# Sheet2.net
KiCad netlist of a schematic drawn in Altium Designer
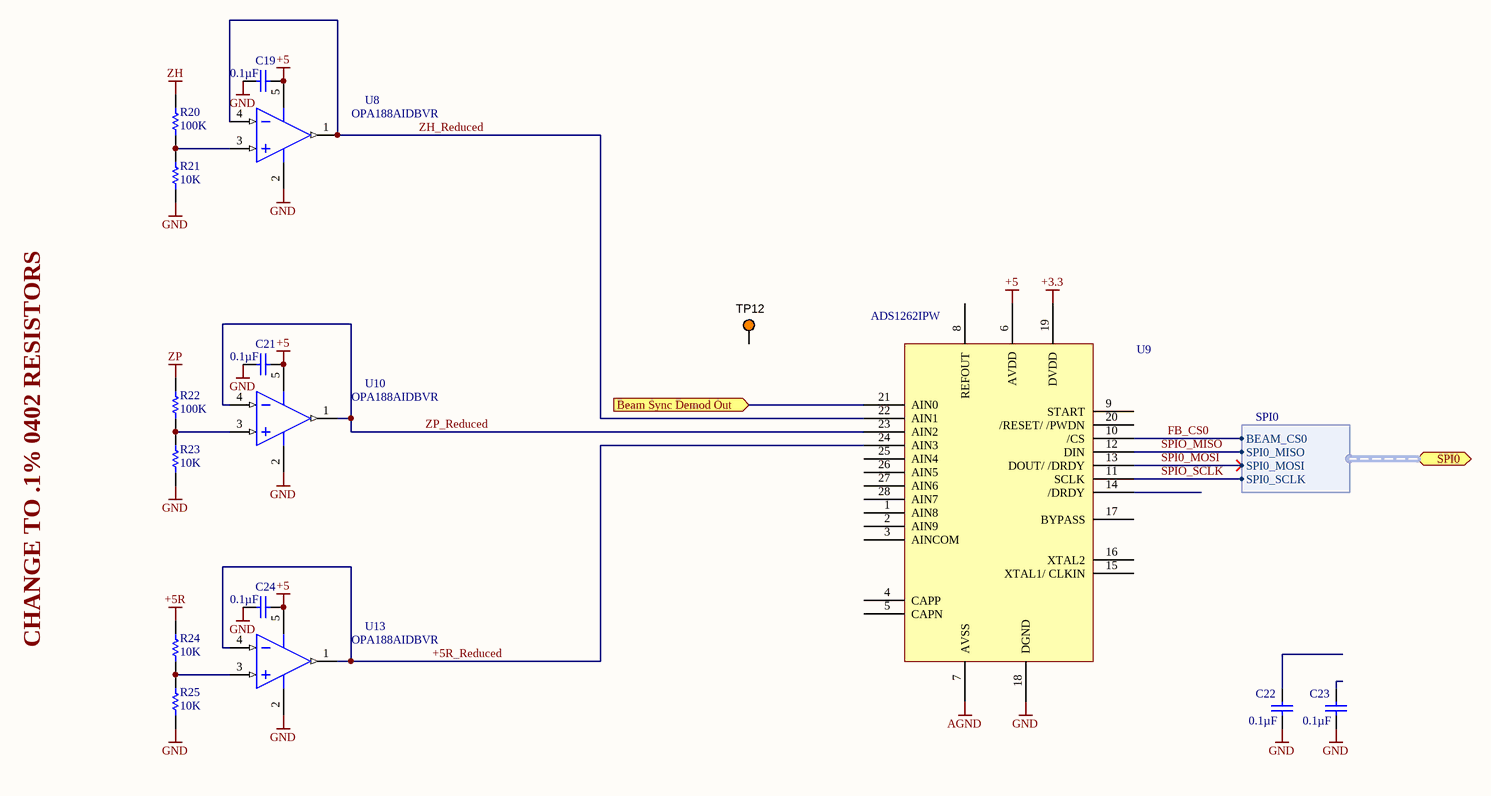
[diagram p0: Sheet2.SchDoc]

(export (version "E")
  (design (tool "Eeschema 10.0.6"))
  (components
    (comp (ref "C19")
      (value "CAP CER 0.1UF 25V X7R 0805")
      (footprint "CAPC0805(2012)145_N")
      (fields
        (field (name "MANUFACTURER") "Murata Electronics North America")
        (field (name "MANUFACTURER PART NUMBER") "GRM21BR71E104KA01L")
        (field (name "CAPACITANCE") "0.1µF")
        (field (name "TOLERANCE") "±10%")
      )
      (libsource (lib "Altium Content Vault") (part "CMP-1036-04795-1"))
    )
    (comp (ref "C21")
      (value "CAP CER 0.1UF 25V X7R 0805")
      (footprint "CAPC0805(2012)145_N")
      (fields
        (field (name "MANUFACTURER") "Murata Electronics North America")
        (field (name "MANUFACTURER PART NUMBER") "GRM21BR71E104KA01L")
        (field (name "CAPACITANCE") "0.1µF")
        (field (name "TOLERANCE") "±10%")
      )
      (libsource (lib "Altium Content Vault") (part "CMP-1036-04795-1"))
    )
    (comp (ref "C22")
      (value "CAP CER 0.1UF 25V X7R 0805")
      (footprint "CAPC0805(2012)145_N")
      (fields
        (field (name "MANUFACTURER") "Murata Electronics North America")
        (field (name "MANUFACTURER PART NUMBER") "GRM21BR71E104KA01L")
        (field (name "CAPACITANCE") "0.1µF")
        (field (name "TOLERANCE") "±10%")
      )
      (libsource (lib "Altium Content Vault") (part "CMP-1036-04795-1"))
    )
    (comp (ref "C23")
      (value "CAP CER 0.1UF 25V X7R 0805")
      (footprint "CAPC0805(2012)145_N")
      (fields
        (field (name "MANUFACTURER") "Murata Electronics North America")
        (field (name "MANUFACTURER PART NUMBER") "GRM21BR71E104KA01L")
        (field (name "CAPACITANCE") "0.1µF")
        (field (name "TOLERANCE") "±10%")
      )
      (libsource (lib "Altium Content Vault") (part "CMP-1036-04795-1"))
    )
    (comp (ref "C24")
      (value "CAP CER 0.1UF 25V X7R 0805")
      (footprint "CAPC0805(2012)145_N")
      (fields
        (field (name "MANUFACTURER") "Murata Electronics North America")
        (field (name "MANUFACTURER PART NUMBER") "GRM21BR71E104KA01L")
        (field (name "CAPACITANCE") "0.1µF")
        (field (name "TOLERANCE") "±10%")
      )
      (libsource (lib "Altium Content Vault") (part "CMP-1036-04795-1"))
    )
    (comp (ref "R20")
      (value "100K")
      (footprint "RESC0805(2012)_L")
      (description "RES SMD 100K OHM 1% 1/8W 0805")
      (fields
        (field (name "MANUFACTURER") "Vishay Dale")
        (field (name "MANUFACTURER PART NUMBER") "RCA0805100KFKEA")
      )
      (libsource (lib "Altium Content Vault") (part "CMP-1013-00215-1"))
    )
    (comp (ref "R21")
      (value "10K")
      (footprint "RESC0805(2012)_L")
      (description "RES SMD 10K OHM 1% 1/8W 0805")
      (fields
        (field (name "MANUFACTURER") "Vishay Dale")
        (field (name "MANUFACTURER PART NUMBER") "CRCW080510K0FKEA")
      )
      (libsource (lib "Altium Content Vault") (part "CMP-1013-00215-1"))
    )
    (comp (ref "R22")
      (value "100K")
      (footprint "RESC0805(2012)_L")
      (description "RES SMD 100K OHM 1% 1/8W 0805")
      (fields
        (field (name "MANUFACTURER") "Vishay Dale")
        (field (name "MANUFACTURER PART NUMBER") "RCA0805100KFKEA")
      )
      (libsource (lib "Altium Content Vault") (part "CMP-1013-00215-1"))
    )
    (comp (ref "R23")
      (value "10K")
      (footprint "RESC0805(2012)_L")
      (description "RES SMD 10K OHM 1% 1/8W 0805")
      (fields
        (field (name "MANUFACTURER") "Vishay Dale")
        (field (name "MANUFACTURER PART NUMBER") "CRCW080510K0FKEA")
      )
      (libsource (lib "Altium Content Vault") (part "CMP-1013-00215-1"))
    )
    (comp (ref "R24")
      (value "10K")
      (footprint "RESC0805(2012)_L")
      (description "RES SMD 10K OHM 1% 1/8W 0805")
      (fields
        (field (name "MANUFACTURER") "Vishay Dale")
        (field (name "MANUFACTURER PART NUMBER") "CRCW080510K0FKEA")
      )
      (libsource (lib "Altium Content Vault") (part "CMP-1013-00215-1"))
    )
    (comp (ref "R25")
      (value "10K")
      (footprint "RESC0805(2012)_L")
      (description "RES SMD 10K OHM 1% 1/8W 0805")
      (fields
        (field (name "MANUFACTURER") "Vishay Dale")
        (field (name "MANUFACTURER PART NUMBER") "CRCW080510K0FKEA")
      )
      (libsource (lib "Altium Content Vault") (part "CMP-1013-00215-1"))
    )
    (comp (ref "TP12")
      (value "5003")
      (footprint "KSTN-5003")
      (description "Test Point, Orange, 1-Pin THD, RoHS")
      (libsource (lib "Altium Content Vault") (part "CMP-1672-00009-1"))
    )
    (comp (ref "U8")
      (value "OPA188AIDBVR")
      (footprint "DBV0005A_M")
      (fields (field (name "MANUFACTURER") "Texas Instruments"))
      (libsource (lib "Altium Content Vault") (part "CMP-0809-00005-2"))
    )
    (comp (ref "U9")
      (value "ADS1262")
      (footprint "ADS1262")
      (description "32 bit Analog to Digital Converter")
      (fields
        (field (name "SUPPLIER PART NUMBER 1") "ADS1262IPW")
        (field (name "MANUFACTURER") "Texas Instruments")
        (field (name "MANUFACTURER PART NUMBER") "ADS1262IPW")
      )
      (libsource (lib "ZLS_Schematic_lib") (part "ADS1262"))
    )
    (comp (ref "U10")
      (value "OPA188AIDBVR")
      (footprint "DBV0005A_M")
      (fields (field (name "MANUFACTURER") "Texas Instruments"))
      (libsource (lib "Altium Content Vault") (part "CMP-0809-00005-2"))
    )
    (comp (ref "U13")
      (value "OPA188AIDBVR")
      (footprint "DBV0005A_M")
      (fields (field (name "MANUFACTURER") "Texas Instruments"))
      (libsource (lib "Altium Content Vault") (part "CMP-0809-00005-2"))
    )
  )
  (nets
    (net (code "2") (name "+3.3") (class "Default")
      (node (ref "U9") (pin "19") (pinfunction "DVDD_19") (pintype "passive"))
    )
    (net (code "3") (name "+5") (class "Default")
      (node (ref "C19") (pin "2") (pinfunction "2_2") (pintype "passive"))
      (node (ref "C21") (pin "2") (pinfunction "2_2") (pintype "passive"))
      (node (ref "C24") (pin "2") (pinfunction "2_2") (pintype "passive"))
      (node (ref "U10") (pin "5") (pinfunction "V+_5") (pintype "power_in"))
      (node (ref "U13") (pin "5") (pinfunction "V+_5") (pintype "power_in"))
      (node (ref "U8") (pin "5") (pinfunction "V+_5") (pintype "power_in"))
      (node (ref "U9") (pin "6") (pinfunction "AVDD_6") (pintype "passive"))
    )
    (net (code "4") (name "+5R") (class "Default")
      (node (ref "R24") (pin "2") (pinfunction "2_2") (pintype "passive"))
    )
    (net (code "5") (name "/+5R_Reduced") (class "Default")
      (node (ref "U13") (pin "1") (pinfunction "OUT_1") (pintype "output"))
      (node (ref "U13") (pin "4") (pinfunction "IN-_4") (pintype "input"))
      (node (ref "U9") (pin "24") (pinfunction "AIN3_24") (pintype "passive"))
    )
    (net (code "6") (name "/Beam Sync Demod Out") (class "Default")
      (node (ref "U9") (pin "21") (pinfunction "AIN0_21") (pintype "passive"))
    )
    (net (code "7") (name "/FB_CS0") (class "Default")
      (node (ref "U9") (pin "10") (pinfunction "/CS_10") (pintype "passive"))
    )
    (net (code "8") (name "/SPI0_MOSI") (class "Default")
      (node (ref "U9") (pin "13") (pinfunction "DOUT/_/DRDY_13") (pintype "passive+no_connect"))
    )
    (net (code "9") (name "/SPIO_MISO") (class "Default")
      (node (ref "U9") (pin "12") (pinfunction "DIN_12") (pintype "passive"))
    )
    (net (code "10") (name "/SPIO_SCLK") (class "Default")
      (node (ref "U9") (pin "11") (pinfunction "SCLK_11") (pintype "passive"))
    )
    (net (code "11") (name "/ZH_Reduced") (class "Default")
      (node (ref "U8") (pin "1") (pinfunction "OUT_1") (pintype "output"))
      (node (ref "U8") (pin "4") (pinfunction "IN-_4") (pintype "input"))
      (node (ref "U9") (pin "22") (pinfunction "AIN1_22") (pintype "passive"))
    )
    (net (code "12") (name "/ZP_Reduced") (class "Default")
      (node (ref "U10") (pin "1") (pinfunction "OUT_1") (pintype "output"))
      (node (ref "U10") (pin "4") (pinfunction "IN-_4") (pintype "input"))
      (node (ref "U9") (pin "23") (pinfunction "AIN2_23") (pintype "passive"))
    )
    (net (code "14") (name "AGND") (class "Default")
      (node (ref "U9") (pin "7") (pinfunction "AVSS_7") (pintype "passive"))
    )
    (net (code "15") (name "GND") (class "Default")
      (node (ref "C19") (pin "1") (pinfunction "1_1") (pintype "passive"))
      (node (ref "C21") (pin "1") (pinfunction "1_1") (pintype "passive"))
      (node (ref "C22") (pin "2") (pinfunction "2_2") (pintype "passive"))
      (node (ref "C23") (pin "2") (pinfunction "2_2") (pintype "passive"))
      (node (ref "C24") (pin "1") (pinfunction "1_1") (pintype "passive"))
      (node (ref "R21") (pin "1") (pinfunction "1_1") (pintype "passive"))
      (node (ref "R23") (pin "1") (pinfunction "1_1") (pintype "passive"))
      (node (ref "R25") (pin "1") (pinfunction "1_1") (pintype "passive"))
      (node (ref "U10") (pin "2") (pinfunction "V-_2") (pintype "power_in"))
      (node (ref "U13") (pin "2") (pinfunction "V-_2") (pintype "power_in"))
      (node (ref "U8") (pin "2") (pinfunction "V-_2") (pintype "power_in"))
      (node (ref "U9") (pin "18") (pinfunction "DGND_18") (pintype "passive"))
    )
    (net (code "16") (name "Net-(U8-IN+)") (class "Default")
      (node (ref "R20") (pin "1") (pinfunction "1_1") (pintype "passive"))
      (node (ref "R21") (pin "2") (pinfunction "2_2") (pintype "passive"))
      (node (ref "U8") (pin "3") (pinfunction "IN+_3") (pintype "input"))
    )
    (net (code "17") (name "Net-(U10-IN+)") (class "Default")
      (node (ref "R22") (pin "1") (pinfunction "1_1") (pintype "passive"))
      (node (ref "R23") (pin "2") (pinfunction "2_2") (pintype "passive"))
      (node (ref "U10") (pin "3") (pinfunction "IN+_3") (pintype "input"))
    )
    (net (code "18") (name "Net-(U13-IN+)") (class "Default")
      (node (ref "R24") (pin "1") (pinfunction "1_1") (pintype "passive"))
      (node (ref "R25") (pin "2") (pinfunction "2_2") (pintype "passive"))
      (node (ref "U13") (pin "3") (pinfunction "IN+_3") (pintype "input"))
    )
    (net (code "19") (name "ZH") (class "Default")
      (node (ref "R20") (pin "2") (pinfunction "2_2") (pintype "passive"))
    )
    (net (code "20") (name "ZP") (class "Default")
      (node (ref "R22") (pin "2") (pinfunction "2_2") (pintype "passive"))
    )
    (net (code "21") (name "unconnected-(C22-Pad1)") (class "Default")
      (node (ref "C22") (pin "1") (pinfunction "1_1") (pintype "passive"))
    )
    (net (code "22") (name "unconnected-(C23-Pad1)") (class "Default")
      (node (ref "C23") (pin "1") (pinfunction "1_1") (pintype "passive"))
    )
    (net (code "23") (name "unconnected-(TP12-Pad1)") (class "Default")
      (node (ref "TP12") (pin "1") (pinfunction "1_1") (pintype "passive"))
    )
    (net (code "24") (name "unconnected-(U9-AIN4-Pad25)") (class "Default")
      (node (ref "U9") (pin "25") (pinfunction "AIN4_25") (pintype "passive"))
    )
    (net (code "25") (name "unconnected-(U9-AIN5-Pad26)") (class "Default")
      (node (ref "U9") (pin "26") (pinfunction "AIN5_26") (pintype "passive"))
    )
    (net (code "26") (name "unconnected-(U9-AIN6-Pad27)") (class "Default")
      (node (ref "U9") (pin "27") (pinfunction "AIN6_27") (pintype "passive"))
    )
    (net (code "27") (name "unconnected-(U9-AIN7-Pad28)") (class "Default")
      (node (ref "U9") (pin "28") (pinfunction "AIN7_28") (pintype "passive"))
    )
    (net (code "28") (name "unconnected-(U9-AIN8-Pad1)") (class "Default")
      (node (ref "U9") (pin "1") (pinfunction "AIN8_1") (pintype "passive"))
    )
    (net (code "29") (name "unconnected-(U9-AIN9-Pad2)") (class "Default")
      (node (ref "U9") (pin "2") (pinfunction "AIN9_2") (pintype "passive"))
    )
    (net (code "30") (name "unconnected-(U9-AINCOM-Pad3)") (class "Default")
      (node (ref "U9") (pin "3") (pinfunction "AINCOM_3") (pintype "passive"))
    )
    (net (code "31") (name "unconnected-(U9-BYPASS-Pad17)") (class "Default")
      (node (ref "U9") (pin "17") (pinfunction "BYPASS_17") (pintype "passive"))
    )
    (net (code "32") (name "unconnected-(U9-CAPN-Pad5)") (class "Default")
      (node (ref "U9") (pin "5") (pinfunction "CAPN_5") (pintype "passive"))
    )
    (net (code "33") (name "unconnected-(U9-CAPP-Pad4)") (class "Default")
      (node (ref "U9") (pin "4") (pinfunction "CAPP_4") (pintype "passive"))
    )
    (net (code "34") (name "unconnected-(U9-REFOUT-Pad8)") (class "Default")
      (node (ref "U9") (pin "8") (pinfunction "REFOUT_8") (pintype "passive"))
    )
    (net (code "35") (name "unconnected-(U9-START-Pad9)") (class "Default")
      (node (ref "U9") (pin "9") (pinfunction "START_9") (pintype "passive"))
    )
    (net (code "36") (name "unconnected-(U9-XTAL1{slash}_CLKIN-Pad15)") (class "Default")
      (node (ref "U9") (pin "15") (pinfunction "XTAL1/_CLKIN_15") (pintype "passive"))
    )
    (net (code "37") (name "unconnected-(U9-XTAL2-Pad16)") (class "Default")
      (node (ref "U9") (pin "16") (pinfunction "XTAL2_16") (pintype "passive"))
    )
    (net (code "38") (name "unconnected-(U9-{slash}DRDY-Pad14)") (class "Default")
      (node (ref "U9") (pin "14") (pinfunction "/DRDY_14") (pintype "passive"))
    )
    (net (code "39") (name "unconnected-(U9-{slash}RESET{slash}_{slash}PWDN-Pad20)") (class "Default")
      (node (ref "U9") (pin "20") (pinfunction "/RESET/_/PWDN_20") (pintype "passive"))
    )
  )
)
